# Nathan_Project-Speaker.net
KiCad netlist of a schematic drawn in EAGLE
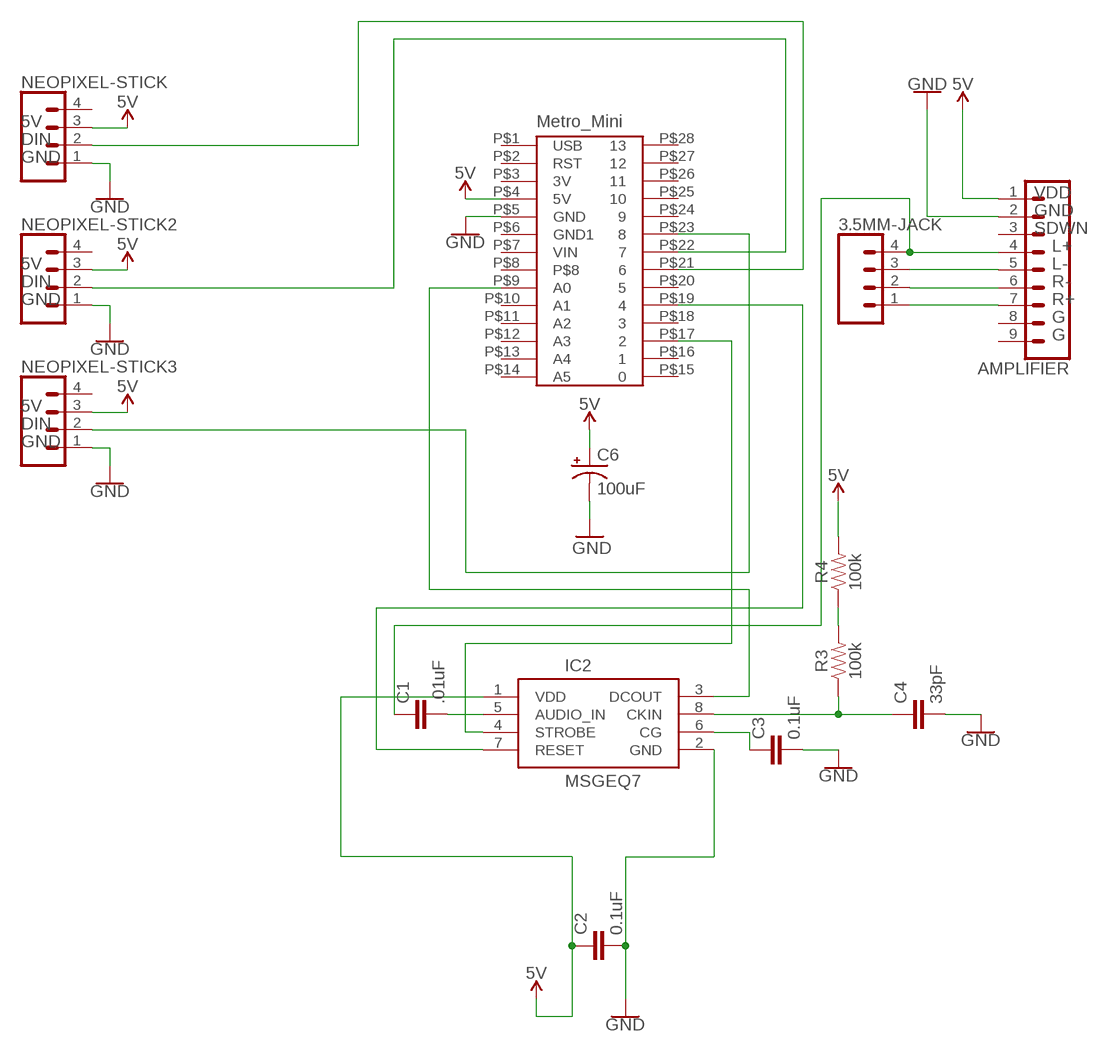
[diagram p0: schematic, sheet 1]

(export (version "E")
  (design (tool "Eeschema 10.0.6"))
  (components
    (comp (ref "3.5MM-JACK")
      (value "CONN_04LOCK_LONGPADS")
      (footprint "eagle-import:1X04_LOCK_LONGPADS")
      (libsource (lib "eagle-import") (part "CONN_04LOCK_LONGPADS"))
    )
    (comp (ref "AMPLIFIER")
      (value "CONN_09LOCK-LONGPADS")
      (footprint "eagle-import:1X09_LOCK_LONGPADS")
      (libsource (lib "eagle-import") (part "CONN_09LOCK-LONGPADS"))
    )
    (comp (ref "C1")
      (value ".01uF")
      (footprint "eagle-import:C5B2.5")
      (libsource (lib "eagle-import") (part "C5/2.5"))
    )
    (comp (ref "C2")
      (value "0.1uF")
      (footprint "eagle-import:C5B2.5")
      (libsource (lib "eagle-import") (part "C5/2.5"))
    )
    (comp (ref "C3")
      (value "0.1uF")
      (footprint "eagle-import:C5B2.5")
      (libsource (lib "eagle-import") (part "C5/2.5"))
    )
    (comp (ref "C4")
      (value "33pF")
      (footprint "eagle-import:C5B2.5")
      (libsource (lib "eagle-import") (part "C5/2.5"))
    )
    (comp (ref "C6")
      (value "100uF")
      (footprint "eagle-import:CPOL-RADIAL-2.5MM-6.5MM")
      (libsource (lib "eagle-import") (part "100UF-POLAR-RADIAL-2.5MM-25V-20%"))
    )
    (comp (ref "IC2")
      (value "MSGEQ7P")
      (footprint "eagle-import:DIP08")
      (libsource (lib "eagle-import") (part "MSGEQ7DIL"))
    )
    (comp (ref "NEOPIXEL-STICK")
      (value "CONN_04LOCK_LONGPADS")
      (footprint "eagle-import:1X04_LOCK_LONGPADS")
      (libsource (lib "eagle-import") (part "CONN_04LOCK_LONGPADS"))
    )
    (comp (ref "NEOPIXEL-STICK2")
      (value "CONN_04LOCK_LONGPADS")
      (footprint "eagle-import:1X04_LOCK_LONGPADS")
      (libsource (lib "eagle-import") (part "CONN_04LOCK_LONGPADS"))
    )
    (comp (ref "NEOPIXEL-STICK3")
      (value "CONN_04LOCK_LONGPADS")
      (footprint "eagle-import:1X04_LOCK_LONGPADS")
      (libsource (lib "eagle-import") (part "CONN_04LOCK_LONGPADS"))
    )
    (comp (ref "R3")
      (value "100k")
      (footprint "eagle-import:AXIAL-0.3")
      (libsource (lib "eagle-import") (part "100KOHM-HORIZ-1/4W-1%"))
    )
    (comp (ref "R4")
      (value "100k")
      (footprint "eagle-import:AXIAL-0.3")
      (libsource (lib "eagle-import") (part "100KOHM-HORIZ-1/4W-1%"))
    )
    (comp (ref "U$2")
      (value "METRO-MINI")
      (footprint "eagle-import:METRO-MINI")
      (libsource (lib "eagle-import") (part "METRO-MINI"))
    )
  )
  (nets
    (net (code "1") (name "5V") (class "Default")
      (node (ref "AMPLIFIER") (pin "1") (pinfunction "1_1") (pintype "passive"))
      (node (ref "C2") (pin "1") (pinfunction "1_1") (pintype "passive"))
      (node (ref "C6") (pin "1") (pinfunction "+_1") (pintype "passive"))
      (node (ref "IC2") (pin "1") (pinfunction "VDD_1") (pintype "input"))
      (node (ref "NEOPIXEL-STICK") (pin "3") (pinfunction "3_3") (pintype "passive"))
      (node (ref "NEOPIXEL-STICK2") (pin "3") (pinfunction "3_3") (pintype "passive"))
      (node (ref "NEOPIXEL-STICK3") (pin "3") (pinfunction "3_3") (pintype "passive"))
      (node (ref "R4") (pin "P$2") (pinfunction "2_P$2") (pintype "passive"))
      (node (ref "U$2") (pin "P$4") (pinfunction "5V_P$4") (pintype "bidirectional"))
    )
    (net (code "2") (name "GND") (class "Default")
      (node (ref "AMPLIFIER") (pin "2") (pinfunction "2_2") (pintype "passive"))
      (node (ref "C2") (pin "2") (pinfunction "2_2") (pintype "passive"))
      (node (ref "C3") (pin "2") (pinfunction "2_2") (pintype "passive"))
      (node (ref "C4") (pin "2") (pinfunction "2_2") (pintype "passive"))
      (node (ref "C6") (pin "2") (pinfunction "-_2") (pintype "passive"))
      (node (ref "IC2") (pin "2") (pinfunction "GND_2") (pintype "bidirectional"))
      (node (ref "NEOPIXEL-STICK") (pin "1") (pinfunction "1_1") (pintype "passive"))
      (node (ref "NEOPIXEL-STICK2") (pin "1") (pinfunction "1_1") (pintype "passive"))
      (node (ref "NEOPIXEL-STICK3") (pin "1") (pinfunction "1_1") (pintype "passive"))
      (node (ref "U$2") (pin "P$5") (pinfunction "GND_P$5") (pintype "bidirectional"))
    )
    (net (code "3") (name "Net-(3.5MM-JACK-Pad1)") (class "Default")
      (node (ref "3.5MM-JACK") (pin "1") (pinfunction "1_1") (pintype "passive"))
      (node (ref "AMPLIFIER") (pin "7") (pinfunction "7_7") (pintype "passive"))
    )
    (net (code "4") (name "Net-(3.5MM-JACK-Pad2)") (class "Default")
      (node (ref "3.5MM-JACK") (pin "2") (pinfunction "2_2") (pintype "passive"))
      (node (ref "AMPLIFIER") (pin "6") (pinfunction "6_6") (pintype "passive"))
    )
    (net (code "5") (name "Net-(3.5MM-JACK-Pad3)") (class "Default")
      (node (ref "3.5MM-JACK") (pin "3") (pinfunction "3_3") (pintype "passive"))
      (node (ref "AMPLIFIER") (pin "5") (pinfunction "5_5") (pintype "passive"))
    )
    (net (code "6") (name "Net-(3.5MM-JACK-Pad4)") (class "Default")
      (node (ref "3.5MM-JACK") (pin "4") (pinfunction "4_4") (pintype "passive"))
      (node (ref "AMPLIFIER") (pin "4") (pinfunction "4_4") (pintype "passive"))
      (node (ref "C1") (pin "1") (pinfunction "1_1") (pintype "passive"))
    )
    (net (code "7") (name "Net-(IC2-AUDIO_IN)") (class "Default")
      (node (ref "C1") (pin "2") (pinfunction "2_2") (pintype "passive"))
      (node (ref "IC2") (pin "5") (pinfunction "AUDIO_IN_5") (pintype "input"))
    )
    (net (code "8") (name "Net-(IC2-CG)") (class "Default")
      (node (ref "C3") (pin "1") (pinfunction "1_1") (pintype "passive"))
      (node (ref "IC2") (pin "6") (pinfunction "CG_6") (pintype "bidirectional"))
    )
    (net (code "9") (name "Net-(IC2-CKIN)") (class "Default")
      (node (ref "C4") (pin "1") (pinfunction "1_1") (pintype "passive"))
      (node (ref "IC2") (pin "8") (pinfunction "CKIN_8") (pintype "bidirectional"))
      (node (ref "R3") (pin "P$1") (pinfunction "1_P$1") (pintype "passive"))
    )
    (net (code "10") (name "Net-(IC2-DCOUT)") (class "Default")
      (node (ref "IC2") (pin "3") (pinfunction "DCOUT_3") (pintype "bidirectional"))
      (node (ref "U$2") (pin "P$9") (pinfunction "A0_P$9") (pintype "bidirectional"))
    )
    (net (code "11") (name "Net-(IC2-RESET)") (class "Default")
      (node (ref "IC2") (pin "7") (pinfunction "RESET_7") (pintype "input"))
      (node (ref "U$2") (pin "P$19") (pinfunction "4_P$19") (pintype "bidirectional"))
    )
    (net (code "12") (name "Net-(IC2-STROBE)") (class "Default")
      (node (ref "IC2") (pin "4") (pinfunction "STROBE_4") (pintype "input"))
      (node (ref "U$2") (pin "P$17") (pinfunction "2_P$17") (pintype "bidirectional"))
    )
    (net (code "13") (name "Net-(R3-2)") (class "Default")
      (node (ref "R3") (pin "P$2") (pinfunction "2_P$2") (pintype "passive"))
      (node (ref "R4") (pin "P$1") (pinfunction "1_P$1") (pintype "passive"))
    )
    (net (code "14") (name "Net-(U$2-6)") (class "Default")
      (node (ref "NEOPIXEL-STICK") (pin "2") (pinfunction "2_2") (pintype "passive"))
      (node (ref "U$2") (pin "P$21") (pinfunction "6_P$21") (pintype "bidirectional"))
    )
    (net (code "15") (name "Net-(U$2-7)") (class "Default")
      (node (ref "NEOPIXEL-STICK2") (pin "2") (pinfunction "2_2") (pintype "passive"))
      (node (ref "U$2") (pin "P$22") (pinfunction "7_P$22") (pintype "bidirectional"))
    )
    (net (code "16") (name "Net-(U$2-8)") (class "Default")
      (node (ref "NEOPIXEL-STICK3") (pin "2") (pinfunction "2_2") (pintype "passive"))
      (node (ref "U$2") (pin "P$23") (pinfunction "8_P$23") (pintype "bidirectional"))
    )
    (net (code "17") (name "unconnected-(AMPLIFIER-Pad3)") (class "Default")
      (node (ref "AMPLIFIER") (pin "3") (pinfunction "3_3") (pintype "passive"))
    )
    (net (code "18") (name "unconnected-(AMPLIFIER-Pad8)") (class "Default")
      (node (ref "AMPLIFIER") (pin "8") (pinfunction "8_8") (pintype "passive"))
    )
    (net (code "19") (name "unconnected-(AMPLIFIER-Pad9)") (class "Default")
      (node (ref "AMPLIFIER") (pin "9") (pinfunction "9_9") (pintype "passive"))
    )
    (net (code "20") (name "unconnected-(NEOPIXEL-STICK-Pad4)") (class "Default")
      (node (ref "NEOPIXEL-STICK") (pin "4") (pinfunction "4_4") (pintype "passive"))
    )
    (net (code "21") (name "unconnected-(NEOPIXEL-STICK2-Pad4)") (class "Default")
      (node (ref "NEOPIXEL-STICK2") (pin "4") (pinfunction "4_4") (pintype "passive"))
    )
    (net (code "22") (name "unconnected-(NEOPIXEL-STICK3-Pad4)") (class "Default")
      (node (ref "NEOPIXEL-STICK3") (pin "4") (pinfunction "4_4") (pintype "passive"))
    )
    (net (code "23") (name "unconnected-(U$2-0-PadP$15)") (class "Default")
      (node (ref "U$2") (pin "P$15") (pinfunction "0_P$15") (pintype "bidirectional"))
    )
    (net (code "24") (name "unconnected-(U$2-1-PadP$16)") (class "Default")
      (node (ref "U$2") (pin "P$16") (pinfunction "1_P$16") (pintype "bidirectional"))
    )
    (net (code "25") (name "unconnected-(U$2-3-PadP$18)") (class "Default")
      (node (ref "U$2") (pin "P$18") (pinfunction "3_P$18") (pintype "bidirectional"))
    )
    (net (code "26") (name "unconnected-(U$2-3V-PadP$3)") (class "Default")
      (node (ref "U$2") (pin "P$3") (pinfunction "3V_P$3") (pintype "bidirectional"))
    )
    (net (code "27") (name "unconnected-(U$2-5-PadP$20)") (class "Default")
      (node (ref "U$2") (pin "P$20") (pinfunction "5_P$20") (pintype "bidirectional"))
    )
    (net (code "28") (name "unconnected-(U$2-9-PadP$24)") (class "Default")
      (node (ref "U$2") (pin "P$24") (pinfunction "9_P$24") (pintype "bidirectional"))
    )
    (net (code "29") (name "unconnected-(U$2-10-PadP$25)") (class "Default")
      (node (ref "U$2") (pin "P$25") (pinfunction "10_P$25") (pintype "bidirectional"))
    )
    (net (code "30") (name "unconnected-(U$2-11-PadP$26)") (class "Default")
      (node (ref "U$2") (pin "P$26") (pinfunction "11_P$26") (pintype "bidirectional"))
    )
    (net (code "31") (name "unconnected-(U$2-12-PadP$27)") (class "Default")
      (node (ref "U$2") (pin "P$27") (pinfunction "12_P$27") (pintype "bidirectional"))
    )
    (net (code "32") (name "unconnected-(U$2-13-PadP$28)") (class "Default")
      (node (ref "U$2") (pin "P$28") (pinfunction "13_P$28") (pintype "bidirectional"))
    )
    (net (code "33") (name "unconnected-(U$2-A1-PadP$10)") (class "Default")
      (node (ref "U$2") (pin "P$10") (pinfunction "A1_P$10") (pintype "bidirectional"))
    )
    (net (code "34") (name "unconnected-(U$2-A2-PadP$11)") (class "Default")
      (node (ref "U$2") (pin "P$11") (pinfunction "A2_P$11") (pintype "bidirectional"))
    )
    (net (code "35") (name "unconnected-(U$2-A3-PadP$12)") (class "Default")
      (node (ref "U$2") (pin "P$12") (pinfunction "A3_P$12") (pintype "bidirectional"))
    )
    (net (code "36") (name "unconnected-(U$2-A4-PadP$13)") (class "Default")
      (node (ref "U$2") (pin "P$13") (pinfunction "A4_P$13") (pintype "bidirectional"))
    )
    (net (code "37") (name "unconnected-(U$2-A5-PadP$14)") (class "Default")
      (node (ref "U$2") (pin "P$14") (pinfunction "A5_P$14") (pintype "bidirectional"))
    )
    (net (code "38") (name "unconnected-(U$2-GND1-PadP$6)") (class "Default")
      (node (ref "U$2") (pin "P$6") (pinfunction "GND1_P$6") (pintype "bidirectional"))
    )
    (net (code "39") (name "unconnected-(U$2-PadP$8)") (class "Default")
      (node (ref "U$2") (pin "P$8") (pinfunction "P$8_P$8") (pintype "bidirectional"))
    )
    (net (code "40") (name "unconnected-(U$2-RST-PadP$2)") (class "Default")
      (node (ref "U$2") (pin "P$2") (pinfunction "RST_P$2") (pintype "bidirectional"))
    )
    (net (code "41") (name "unconnected-(U$2-USB-PadP$1)") (class "Default")
      (node (ref "U$2") (pin "P$1") (pinfunction "USB_P$1") (pintype "bidirectional"))
    )
    (net (code "42") (name "unconnected-(U$2-VIN-PadP$7)") (class "Default")
      (node (ref "U$2") (pin "P$7") (pinfunction "VIN_P$7") (pintype "bidirectional"))
    )
  )
)
